# UART_RS485.net
KiCad netlist of a schematic drawn in Altium Designer
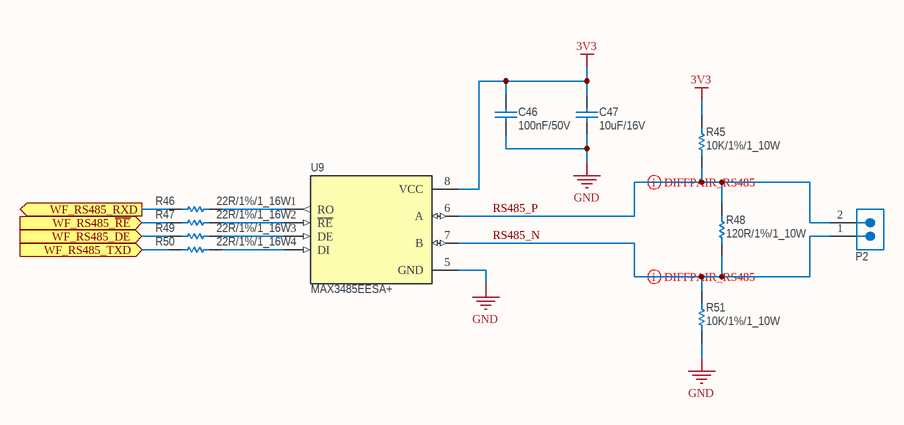
[diagram p0: UART_RS485.SchDoc]

(export (version "E")
  (design (tool "Eeschema 10.0.6"))
  (components
    (comp (ref "C46")
      (value "100nF/50V")
      (footprint "CAP_0603")
      (description "CAP, size 0603, 100nF, 50V")
      (fields (field (name "SUPPLY PART NUMBER") "Tụ Gốm 0603 100nF (0.1uF) 50V"))
      (libsource (lib "BluetoothTracking") (part "Ceramic_Cap_100nF_50V_0603"))
    )
    (comp (ref "C47")
      (value "10uF/16V")
      (footprint "CAP_0603")
      (description "CAP, size 0603, 10uF, 16V")
      (fields (field (name "SUPPLY PART NUMBER") "Tụ Gốm 0603 10uF 16V"))
      (libsource (lib "BluetoothTracking") (part "Ceramic_Cap_10uF_16V_0603"))
    )
    (comp (ref "P2")
      (value "3.81mm_2P")
      (footprint "Terminal_Block_3.81mm_2P")
      (description "Terminal Block THT, pitch 3.81mm, 2p, 300V, 10A")
      (fields
        (field (name "SUPPLY PART NUMBER") "UL-3.81-2-R Terminal Block Plug-in Hàn PCB 2 Chân Cong 3.81mm 300V 10A ULO")
      )
      (libsource (lib "BluetoothTracking") (part "Terminal_Block_3.81mm_2P"))
    )
    (comp (ref "R45")
      (value "10K/1%/1_10W")
      (footprint "Resistor_0603")
      (description "Resistor 0603 10KOhm 1% 1_10W")
      (fields (field (name "SUPPLY PART NUMBER") "Điện Trở 10 KOhm 0603 1%"))
      (libsource (lib "BluetoothTracking") (part "Res_10K_0603_1%"))
    )
    (comp (ref "R46")
      (value "22R/1%/1_16W")
      (footprint "RESISTOR_0402")
      (description "Resistor 0402 22 Ohm 1% 1_16W")
      (libsource (lib "BluetoothTracking") (part "Res_22R_0402_1%"))
    )
    (comp (ref "R47")
      (value "22R/1%/1_16W")
      (footprint "RESISTOR_0402")
      (description "Resistor 0402 22 Ohm 1% 1_16W")
      (libsource (lib "BluetoothTracking") (part "Res_22R_0402_1%"))
    )
    (comp (ref "R48")
      (value "120R/1%/1_10W")
      (footprint "Resistor_0603")
      (description "Resistor 0603 120 Ohm 1% 1_10W")
      (fields (field (name "SUPPLY PART NUMBER") "Điện Trở 120 Ohm 0603 1%"))
      (libsource (lib "BluetoothTracking") (part "Res_120R_0603_1%"))
    )
    (comp (ref "R49")
      (value "22R/1%/1_16W")
      (footprint "RESISTOR_0402")
      (description "Resistor 0402 22 Ohm 1% 1_16W")
      (libsource (lib "BluetoothTracking") (part "Res_22R_0402_1%"))
    )
    (comp (ref "R50")
      (value "22R/1%/1_16W")
      (footprint "RESISTOR_0402")
      (description "Resistor 0402 22 Ohm 1% 1_16W")
      (libsource (lib "BluetoothTracking") (part "Res_22R_0402_1%"))
    )
    (comp (ref "R51")
      (value "10K/1%/1_10W")
      (footprint "Resistor_0603")
      (description "Resistor 0603 10KOhm 1% 1_10W")
      (fields (field (name "SUPPLY PART NUMBER") "Điện Trở 10 KOhm 0603 1%"))
      (libsource (lib "BluetoothTracking") (part "Res_10K_0603_1%"))
    )
    (comp (ref "U9")
      (value "MAX3485EESA+")
      (footprint "SOIC-8")
      (description "1/1 Transceiver Half RS422, RS485 8-SOIC")
      (fields (field (name "SUPPLY PART NUMBER") "MAX3485EESA+ Line Transceiver, 8-SOIC"))
      (libsource (lib "BluetoothTracking") (part "MAX3485EESA+"))
    )
  )
  (nets
    (net (code "1") (name "/RS485_N") (class "Default")
      (node (ref "P2") (pin "1") (pinfunction "1_1") (pintype "passive"))
      (node (ref "R48") (pin "1") (pinfunction "1_1") (pintype "passive"))
      (node (ref "R51") (pin "1") (pinfunction "1_1") (pintype "passive"))
      (node (ref "U9") (pin "7") (pinfunction "B_7") (pintype "bidirectional"))
    )
    (net (code "2") (name "/RS485_P") (class "Default")
      (node (ref "P2") (pin "2") (pinfunction "2_2") (pintype "passive"))
      (node (ref "R45") (pin "1") (pinfunction "1_1") (pintype "passive"))
      (node (ref "R48") (pin "2") (pinfunction "2_2") (pintype "passive"))
      (node (ref "U9") (pin "6") (pinfunction "A_6") (pintype "bidirectional"))
    )
    (net (code "3") (name "/WF_RS485_DE") (class "Default")
      (node (ref "R49") (pin "1") (pinfunction "1_1") (pintype "passive"))
    )
    (net (code "4") (name "/WF_RS485_RXD") (class "Default")
      (node (ref "R46") (pin "1") (pinfunction "1_1") (pintype "passive"))
    )
    (net (code "5") (name "/WF_RS485_TXD") (class "Default")
      (node (ref "R50") (pin "1") (pinfunction "1_1") (pintype "passive"))
    )
    (net (code "6") (name "/WF_RS485_~{RE}") (class "Default")
      (node (ref "R47") (pin "1") (pinfunction "1_1") (pintype "passive"))
    )
    (net (code "7") (name "3V3") (class "Default")
      (node (ref "C46") (pin "2") (pinfunction "2_2") (pintype "passive"))
      (node (ref "C47") (pin "2") (pinfunction "2_2") (pintype "passive"))
      (node (ref "R45") (pin "2") (pinfunction "2_2") (pintype "passive"))
      (node (ref "U9") (pin "8") (pinfunction "VCC_8") (pintype "power_in"))
    )
    (net (code "8") (name "GND") (class "Default")
      (node (ref "C46") (pin "1") (pinfunction "1_1") (pintype "passive"))
      (node (ref "C47") (pin "1") (pinfunction "1_1") (pintype "passive"))
      (node (ref "R51") (pin "2") (pinfunction "2_2") (pintype "passive"))
      (node (ref "U9") (pin "5") (pinfunction "GND_5") (pintype "power_in"))
    )
    (net (code "9") (name "Net-(U9-DE)") (class "Default")
      (node (ref "R49") (pin "2") (pinfunction "2_2") (pintype "passive"))
      (node (ref "U9") (pin "3") (pinfunction "DE_3") (pintype "input"))
    )
    (net (code "10") (name "Net-(U9-DI)") (class "Default")
      (node (ref "R50") (pin "2") (pinfunction "2_2") (pintype "passive"))
      (node (ref "U9") (pin "4") (pinfunction "DI_4") (pintype "input"))
    )
    (net (code "11") (name "Net-(U9-RO)") (class "Default")
      (node (ref "R46") (pin "2") (pinfunction "2_2") (pintype "passive"))
      (node (ref "U9") (pin "1") (pinfunction "RO_1") (pintype "output"))
    )
    (net (code "12") (name "Net-(U9-~{RE})") (class "Default")
      (node (ref "R47") (pin "2") (pinfunction "2_2") (pintype "passive"))
      (node (ref "U9") (pin "2") (pinfunction "~{RE}_2") (pintype "input"))
    )
  )
)
